# RoControl.net
KiCad netlist of a schematic drawn in Altium Designer
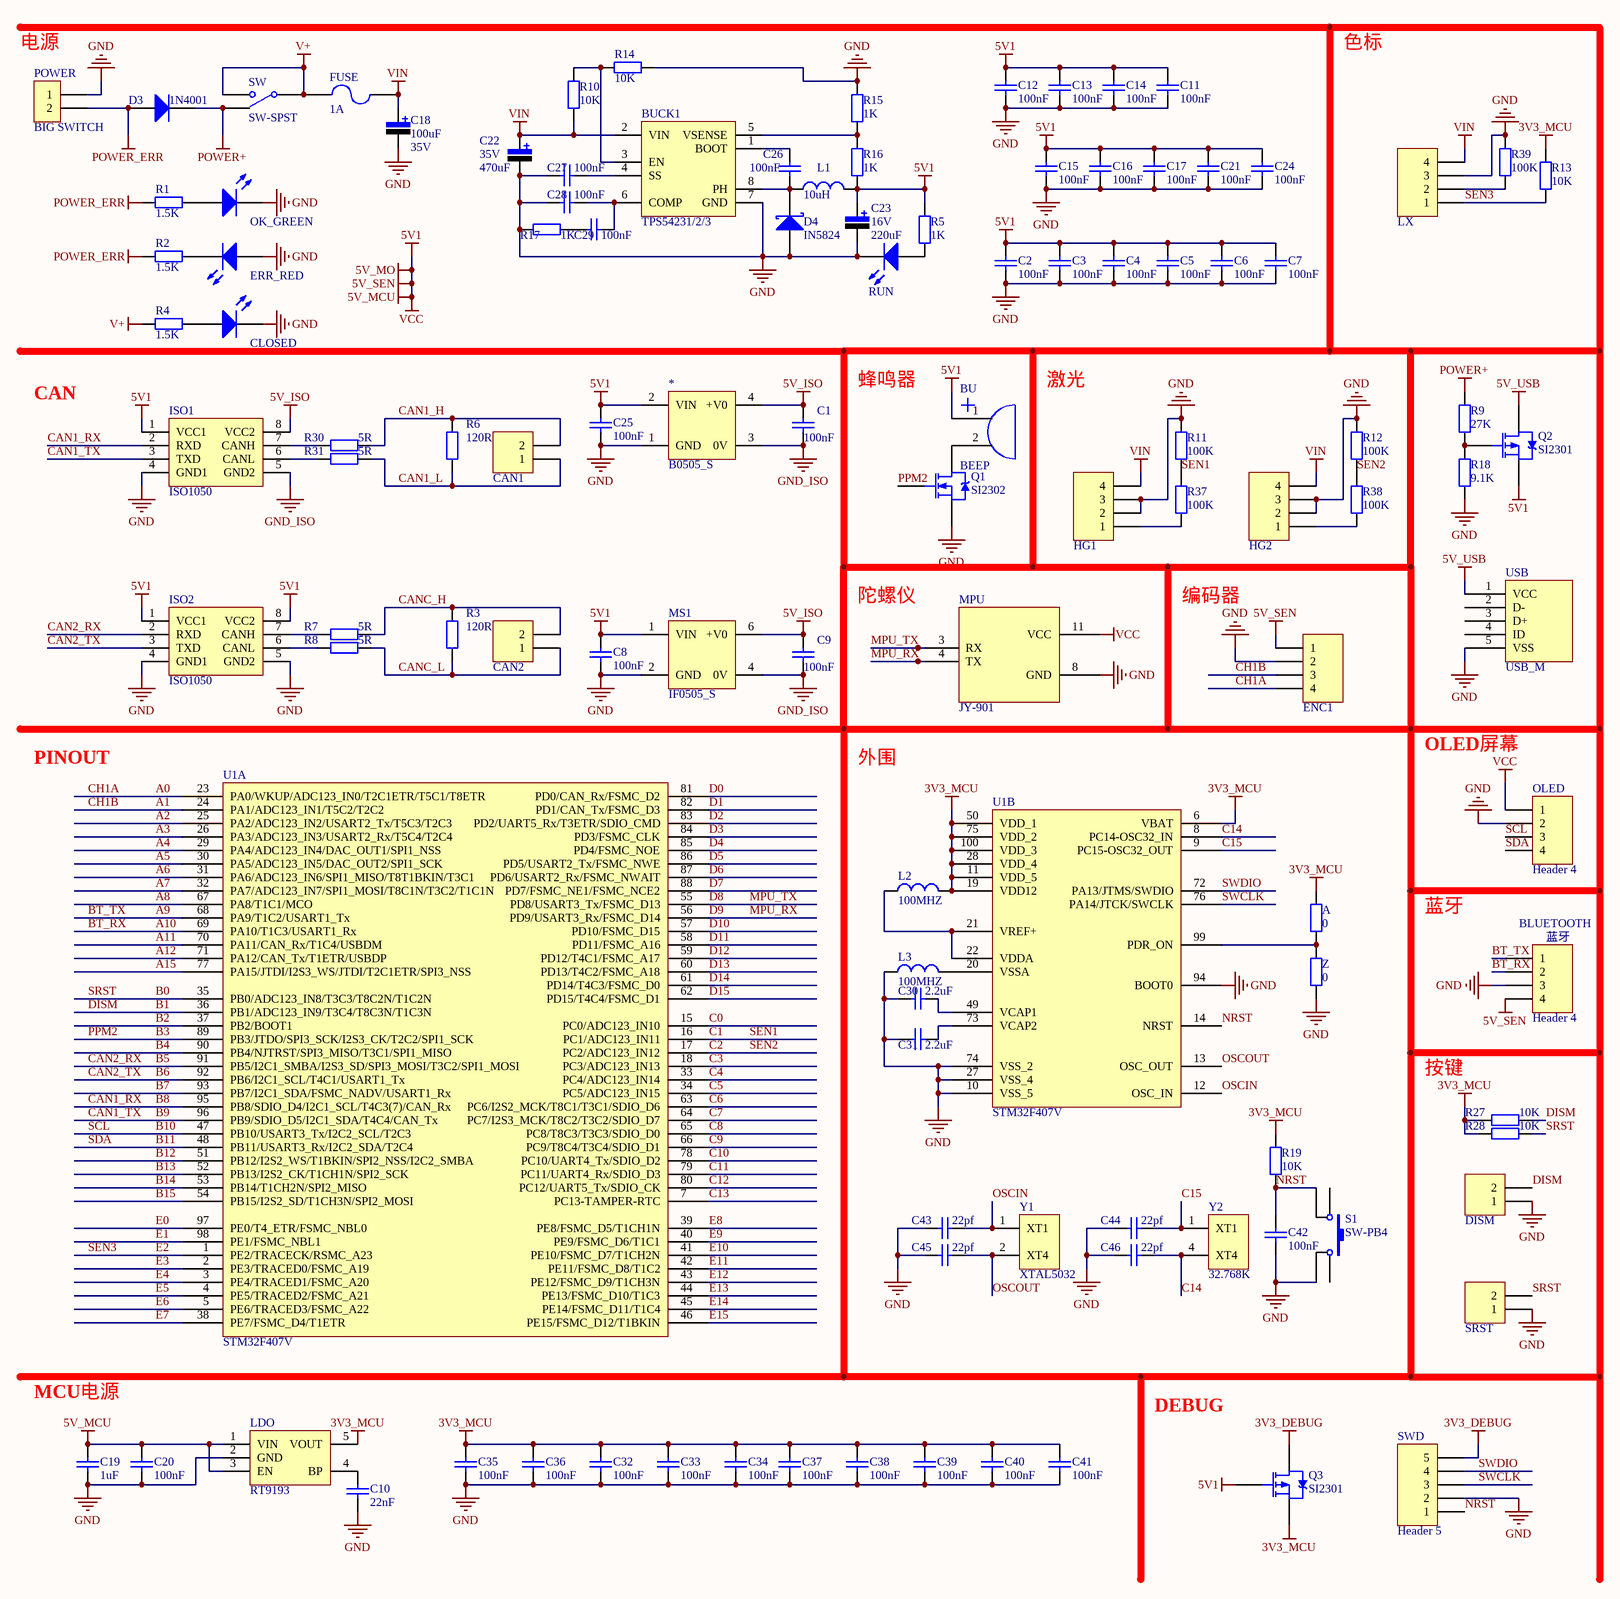
[diagram p0: RoControl.SchDoc]

(export (version "E")
  (design (tool "Eeschema 10.0.6"))
  (components
    (comp (ref "*")
      (value "B0505_S")
      (footprint "MORNSUN_SIP_S")
      (libsource (lib "RobocanControl") (part "B0505_S"))
    )
    (comp (ref "A")
      (value "0")
      (footprint "0603-1")
      (description "贴片电阻")
      (fields (field (name "Comment") "Res1") (field (name "PUBLISHER") "Altium Limited"))
      (libsource (lib "") (part "Res1_3"))
    )
    (comp (ref "BLUETOOTH")
      (value "Header 4")
      (footprint "HDR1X4")
      (description "Header, 4-Pin")
      (fields (field (name "PUBLISHER") "Altium Limited"))
      (libsource (lib "Miscellaneous Connectors") (part "Header 4"))
    )
    (comp (ref "BU")
      (value "BEEP")
      (footprint "CONTROL:BEEP")
      (description "蜂鸣器")
      (libsource (lib "Fszhang") (part "BEEP"))
    )
    (comp (ref "BUCK1")
      (value "TPS54231/2/3")
      (footprint "SOIC8_N")
      (libsource (lib "RobocanControl") (part "TPS54231/2/3"))
    )
    (comp (ref "C1")
      (value "100nF")
      (footprint "CAP-3528")
      (description "无极性电容")
      (fields (field (name "Comment") "Cap") (field (name "PUBLISHER") "Altium Limited"))
      (libsource (lib "Fszhang") (part "Cap"))
    )
    (comp (ref "C2")
      (value "100nF")
      (footprint "CAP-3528")
      (description "无极性电容")
      (fields (field (name "Comment") "Cap") (field (name "PUBLISHER") "Altium Limited"))
      (libsource (lib "Fszhang") (part "Cap"))
    )
    (comp (ref "C3")
      (value "100nF")
      (footprint "CAP-3528")
      (description "无极性电容")
      (fields (field (name "Comment") "Cap") (field (name "PUBLISHER") "Altium Limited"))
      (libsource (lib "Fszhang") (part "Cap"))
    )
    (comp (ref "C4")
      (value "100nF")
      (footprint "C-RAD-0805")
      (description "无极性电容")
      (fields (field (name "Comment") "Cap") (field (name "PUBLISHER") "Altium Limited"))
      (libsource (lib "Fszhang") (part "Cap"))
    )
    (comp (ref "C5")
      (value "100nF")
      (footprint "C-RAD-0805")
      (description "无极性电容")
      (fields (field (name "Comment") "Cap") (field (name "PUBLISHER") "Altium Limited"))
      (libsource (lib "Fszhang") (part "Cap"))
    )
    (comp (ref "C6")
      (value "100nF")
      (footprint "C-RAD-0805")
      (description "无极性电容")
      (fields (field (name "Comment") "Cap") (field (name "PUBLISHER") "Altium Limited"))
      (libsource (lib "Fszhang") (part "Cap"))
    )
    (comp (ref "C7")
      (value "100nF")
      (footprint "C-RAD-0805")
      (description "无极性电容")
      (fields (field (name "Comment") "Cap") (field (name "PUBLISHER") "Altium Limited"))
      (libsource (lib "Fszhang") (part "Cap"))
    )
    (comp (ref "C8")
      (value "100nF")
      (footprint "C-RAD-0805")
      (description "无极性电容")
      (fields (field (name "Comment") "Cap") (field (name "PUBLISHER") "Altium Limited"))
      (libsource (lib "Fszhang") (part "Cap"))
    )
    (comp (ref "C9")
      (value "100nF")
      (footprint "CAP-3528")
      (description "无极性电容")
      (fields (field (name "Comment") "Cap") (field (name "PUBLISHER") "Altium Limited"))
      (libsource (lib "Fszhang") (part "Cap"))
    )
    (comp (ref "C10")
      (value "22nF")
      (footprint "C-RAD-0805")
      (description "无极性电容")
      (fields (field (name "Comment") "Cap") (field (name "PUBLISHER") "Altium Limited"))
      (libsource (lib "Fszhang") (part "Cap"))
    )
    (comp (ref "C11")
      (value "100nF")
      (footprint "CAP-3528")
      (description "无极性电容")
      (fields (field (name "Comment") "Cap") (field (name "PUBLISHER") "Altium Limited"))
      (libsource (lib "Fszhang") (part "Cap"))
    )
    (comp (ref "C12")
      (value "100nF")
      (footprint "CAP-3528")
      (description "无极性电容")
      (fields (field (name "Comment") "Cap") (field (name "PUBLISHER") "Altium Limited"))
      (libsource (lib "Fszhang") (part "Cap"))
    )
    (comp (ref "C13")
      (value "100nF")
      (footprint "CAP-3528")
      (description "无极性电容")
      (fields (field (name "Comment") "Cap") (field (name "PUBLISHER") "Altium Limited"))
      (libsource (lib "Fszhang") (part "Cap"))
    )
    (comp (ref "C14")
      (value "100nF")
      (footprint "CAP-3528")
      (description "无极性电容")
      (fields (field (name "Comment") "Cap") (field (name "PUBLISHER") "Altium Limited"))
      (libsource (lib "Fszhang") (part "Cap"))
    )
    (comp (ref "C15")
      (value "100nF")
      (footprint "CAP-3528")
      (description "无极性电容")
      (fields (field (name "Comment") "Cap") (field (name "PUBLISHER") "Altium Limited"))
      (libsource (lib "Fszhang") (part "Cap"))
    )
    (comp (ref "C16")
      (value "100nF")
      (footprint "CAP-3528")
      (description "无极性电容")
      (fields (field (name "Comment") "Cap") (field (name "PUBLISHER") "Altium Limited"))
      (libsource (lib "Fszhang") (part "Cap"))
    )
    (comp (ref "C17")
      (value "100nF")
      (footprint "CAP-3528")
      (description "无极性电容")
      (fields (field (name "Comment") "Cap") (field (name "PUBLISHER") "Altium Limited"))
      (libsource (lib "Fszhang") (part "Cap"))
    )
    (comp (ref "C18")
      (value "100uF")
      (footprint "CAP-3528")
      (description "极性电解电容")
      (fields
        (field (name "VOL") "35V")
        (field (name "Comment") "Cap Pol")
        (field (name "PUBLISHER") "Altium Limited")
      )
      (libsource (lib "Fszhang") (part "Cap Pol"))
    )
    (comp (ref "C19")
      (value "1uF")
      (footprint "C-RAD-0805")
      (description "无极性电容")
      (fields (field (name "Comment") "Cap") (field (name "PUBLISHER") "Altium Limited"))
      (libsource (lib "Fszhang") (part "Cap"))
    )
    (comp (ref "C20")
      (value "100nF")
      (footprint "C-RAD-0805")
      (description "无极性电容")
      (fields (field (name "Comment") "Cap") (field (name "PUBLISHER") "Altium Limited"))
      (libsource (lib "Fszhang") (part "Cap"))
    )
    (comp (ref "C21")
      (value "100nF")
      (footprint "CAP-3528")
      (description "无极性电容")
      (fields (field (name "Comment") "Cap") (field (name "PUBLISHER") "Altium Limited"))
      (libsource (lib "Fszhang") (part "Cap"))
    )
    (comp (ref "C22")
      (value "470uF")
      (footprint "C-RB-8")
      (description "极性电解电容")
      (fields
        (field (name "VOL") "35V")
        (field (name "Comment") "Cap Pol")
        (field (name "PUBLISHER") "Altium Limited")
      )
      (libsource (lib "Fszhang") (part "Cap Pol"))
    )
    (comp (ref "C23")
      (value "220uF")
      (footprint "C-RB-8")
      (description "极性电解电容")
      (fields
        (field (name "VOL") "16V")
        (field (name "Comment") "Cap Pol")
        (field (name "PUBLISHER") "Altium Limited")
      )
      (libsource (lib "Fszhang") (part "Cap Pol"))
    )
    (comp (ref "C24")
      (value "100nF")
      (footprint "CAP-3528")
      (description "无极性电容")
      (fields (field (name "Comment") "Cap") (field (name "PUBLISHER") "Altium Limited"))
      (libsource (lib "Fszhang") (part "Cap"))
    )
    (comp (ref "C25")
      (value "100nF")
      (footprint "C-RAD-0805")
      (description "无极性电容")
      (fields (field (name "Comment") "Cap") (field (name "PUBLISHER") "Altium Limited"))
      (libsource (lib "Fszhang") (part "Cap"))
    )
    (comp (ref "C26")
      (value "100nF")
      (footprint "C-RAD-0805")
      (description "无极性电容")
      (fields (field (name "Comment") "Cap") (field (name "PUBLISHER") "Altium Limited"))
      (libsource (lib "Fszhang") (part "Cap"))
    )
    (comp (ref "C27")
      (value "100nF")
      (footprint "C-RAD-0805")
      (description "无极性电容")
      (fields (field (name "Comment") "Cap") (field (name "PUBLISHER") "Altium Limited"))
      (libsource (lib "Fszhang") (part "Cap"))
    )
    (comp (ref "C28")
      (value "100nF")
      (footprint "C-RAD-0805")
      (description "无极性电容")
      (fields (field (name "Comment") "Cap") (field (name "PUBLISHER") "Altium Limited"))
      (libsource (lib "Fszhang") (part "Cap"))
    )
    (comp (ref "C29")
      (value "100nF")
      (footprint "C-RAD-0805")
      (description "无极性电容")
      (fields (field (name "Comment") "Cap") (field (name "PUBLISHER") "Altium Limited"))
      (libsource (lib "Fszhang") (part "Cap"))
    )
    (comp (ref "C30")
      (value "2.2uF")
      (footprint "C-RAD-0805")
      (description "无极性电容")
      (fields (field (name "Comment") "Cap") (field (name "PUBLISHER") "Altium Limited"))
      (libsource (lib "Fszhang") (part "Cap"))
    )
    (comp (ref "C31")
      (value "2.2uF")
      (footprint "C-RAD-0805")
      (description "无极性电容")
      (fields (field (name "Comment") "Cap") (field (name "PUBLISHER") "Altium Limited"))
      (libsource (lib "Fszhang") (part "Cap"))
    )
    (comp (ref "C32")
      (value "100nF")
      (footprint "C-RAD-0805")
      (description "无极性电容")
      (fields (field (name "Comment") "Cap") (field (name "PUBLISHER") "Altium Limited"))
      (libsource (lib "Fszhang") (part "Cap"))
    )
    (comp (ref "C33")
      (value "100nF")
      (footprint "C-RAD-0805")
      (description "无极性电容")
      (fields (field (name "Comment") "Cap") (field (name "PUBLISHER") "Altium Limited"))
      (libsource (lib "Fszhang") (part "Cap"))
    )
    (comp (ref "C34")
      (value "100nF")
      (footprint "C-RAD-0805")
      (description "无极性电容")
      (fields (field (name "Comment") "Cap") (field (name "PUBLISHER") "Altium Limited"))
      (libsource (lib "Fszhang") (part "Cap"))
    )
    (comp (ref "C35")
      (value "100nF")
      (footprint "C-RAD-0805")
      (description "无极性电容")
      (fields (field (name "Comment") "Cap") (field (name "PUBLISHER") "Altium Limited"))
      (libsource (lib "Fszhang") (part "Cap"))
    )
    (comp (ref "C36")
      (value "100nF")
      (footprint "C-RAD-0805")
      (description "无极性电容")
      (fields (field (name "Comment") "Cap") (field (name "PUBLISHER") "Altium Limited"))
      (libsource (lib "Fszhang") (part "Cap"))
    )
    (comp (ref "C37")
      (value "100nF")
      (footprint "C-RAD-0805")
      (description "无极性电容")
      (fields (field (name "Comment") "Cap") (field (name "PUBLISHER") "Altium Limited"))
      (libsource (lib "Fszhang") (part "Cap"))
    )
    (comp (ref "C38")
      (value "100nF")
      (footprint "C-RAD-0805")
      (description "无极性电容")
      (fields (field (name "Comment") "Cap") (field (name "PUBLISHER") "Altium Limited"))
      (libsource (lib "Fszhang") (part "Cap"))
    )
    (comp (ref "C39")
      (value "100nF")
      (footprint "C-RAD-0805")
      (description "无极性电容")
      (fields (field (name "Comment") "Cap") (field (name "PUBLISHER") "Altium Limited"))
      (libsource (lib "Fszhang") (part "Cap"))
    )
    (comp (ref "C40")
      (value "100nF")
      (footprint "C-RAD-0805")
      (description "无极性电容")
      (fields (field (name "Comment") "Cap") (field (name "PUBLISHER") "Altium Limited"))
      (libsource (lib "Fszhang") (part "Cap"))
    )
    (comp (ref "C41")
      (value "100nF")
      (footprint "C-RAD-0805")
      (description "无极性电容")
      (fields (field (name "Comment") "Cap") (field (name "PUBLISHER") "Altium Limited"))
      (libsource (lib "Fszhang") (part "Cap"))
    )
    (comp (ref "C42")
      (value "100nF")
      (footprint "C-RAD-0805")
      (description "无极性电容")
      (fields (field (name "Comment") "Cap") (field (name "PUBLISHER") "Altium Limited"))
      (libsource (lib "Fszhang") (part "Cap"))
    )
    (comp (ref "C43")
      (value "22pf")
      (footprint "C-RAD-0603")
      (description "无极性电容")
      (fields (field (name "Comment") "Cap") (field (name "PUBLISHER") "Altium Limited"))
      (libsource (lib "Fszhang") (part "Cap"))
    )
    (comp (ref "C44")
      (value "22pf")
      (footprint "C-RAD-0603")
      (description "无极性电容")
      (fields (field (name "Comment") "Cap") (field (name "PUBLISHER") "Altium Limited"))
      (libsource (lib "Fszhang") (part "Cap"))
    )
    (comp (ref "C45")
      (value "22pf")
      (footprint "C-RAD-0603")
      (description "无极性电容")
      (fields (field (name "Comment") "Cap") (field (name "PUBLISHER") "Altium Limited"))
      (libsource (lib "Fszhang") (part "Cap"))
    )
    (comp (ref "C46")
      (value "22pf")
      (footprint "C-RAD-0603")
      (description "无极性电容")
      (fields (field (name "Comment") "Cap") (field (name "PUBLISHER") "Altium Limited"))
      (libsource (lib "Fszhang") (part "Cap"))
    )
    (comp (ref "CAN1")
      (value "Header 2")
      (footprint "HDR2X1_C")
      (description "接插件")
      (fields (field (name "PUBLISHER") "Altium Limited"))
      (libsource (lib "Fszhang") (part "Header 2"))
    )
    (comp (ref "CAN2")
      (value "Header 2")
      (footprint "HDR2X1_C")
      (description "接插件")
      (fields (field (name "PUBLISHER") "Altium Limited"))
      (libsource (lib "Fszhang") (part "Header 2"))
    )
    (comp (ref "CLOSED")
      (value "LED0")
      (footprint "LED_0805")
      (description "发光二极管")
      (fields (field (name "PUBLISHER") "Altium Limited"))
      (libsource (lib "Fszhang") (part "LED0"))
    )
    (comp (ref "D3")
      (value "Diode")
      (footprint "DIODE-SMA")
      (description "二极管")
      (fields (field (name "TYPE") "1N4001") (field (name "PUBLISHER") "Altium Limited"))
      (libsource (lib "Fszhang") (part "Diode"))
    )
    (comp (ref "D4")
      (value "D-Schottky")
      (footprint "DIODE-1206")
      (description "肖特基二极管")
      (fields (field (name "TYPE") "IN5824") (field (name "PUBLISHER") "Altium Limited"))
      (libsource (lib "Fszhang") (part "D-Schottky"))
    )
    (comp (ref "DISM")
      (value "Header 2")
      (footprint "HDR2X1_B1")
      (description "接插件")
      (fields (field (name "PUBLISHER") "Altium Limited"))
      (libsource (lib "Fszhang") (part "Header 2"))
    )
    (comp (ref "ENC1")
      (value "Header 4")
      (footprint "HDR4X1_B1")
      (description "接插件")
      (fields (field (name "PUBLISHER") "Altium Limited"))
      (libsource (lib "") (part "Header 4_1"))
    )
    (comp (ref "ERR_RED")
      (value "LED0")
      (footprint "LED_0805")
      (description "发光二极管")
      (fields (field (name "PUBLISHER") "Altium Limited"))
      (libsource (lib "Fszhang") (part "LED0"))
    )
    (comp (ref "FUSE")
      (value "1A")
      (footprint "1812")
      (description "保险丝")
      (fields (field (name "Comment") "Fuse") (field (name "PUBLISHER") "Altium Limited"))
      (libsource (lib "Fszhang") (part "Fuse 2"))
    )
    (comp (ref "HG1")
      (value "Header 4")
      (footprint "HDR4X1_B1")
      (description "接插件")
      (fields (field (name "PUBLISHER") "Altium Limited"))
      (libsource (lib "Fszhang") (part "Header 4"))
    )
    (comp (ref "HG2")
      (value "Header 4")
      (footprint "HDR4X1_B1")
      (description "接插件")
      (fields (field (name "PUBLISHER") "Altium Limited"))
      (libsource (lib "Fszhang") (part "Header 4"))
    )
    (comp (ref "ISO1")
      (value "ISO1050")
      (footprint "SOP254P1040X485-8N")
      (libsource (lib "RobocanControl") (part "ISO1050"))
    )
    (comp (ref "ISO2")
      (value "ISO1050")
      (footprint "SOP254P1040X485-8N")
      (libsource (lib "RobocanControl") (part "ISO1050"))
    )
    (comp (ref "L1")
      (value "10uH")
      (footprint "CD54")
      (description "电感")
      (fields (field (name "Comment") "Inductor") (field (name "PUBLISHER") "Altium Limited"))
      (libsource (lib "Fszhang") (part "Inductor"))
    )
    (comp (ref "L2")
      (value "100MHZ")
      (footprint "0805-1")
      (description "电感")
      (fields (field (name "Comment") "Inductor") (field (name "PUBLISHER") "Altium Limited"))
      (libsource (lib "Fszhang") (part "Inductor"))
    )
    (comp (ref "L3")
      (value "100MHZ")
      (footprint "0805-1")
      (description "电感")
      (fields (field (name "Comment") "Inductor") (field (name "PUBLISHER") "Altium Limited"))
      (libsource (lib "Fszhang") (part "Inductor"))
    )
    (comp (ref "LDO")
      (value "RT9193")
      (footprint "SOT104P300X129-5N")
      (libsource (lib "RobocanControl") (part "RT9193"))
    )
    (comp (ref "LX")
      (value "Header 4")
      (footprint "HDR4X1_B1")
      (description "接插件")
      (fields (field (name "PUBLISHER") "Altium Limited"))
      (libsource (lib "Fszhang") (part "Header 4"))
    )
    (comp (ref "MPU")
      (value "JY-901")
      (footprint "JY-901 - duplicate")
      (description "君悦智控高精度9轴传感器")
      (libsource (lib "RobocanControl") (part "JY-901"))
    )
    (comp (ref "MS1")
      (value "IF0505_S")
      (footprint "MORNSUN_SIP_LS")
      (libsource (lib "RobocanControl") (part "IF0505_S"))
    )
    (comp (ref "OK_GREEN")
      (value "LED0")
      (footprint "LED_0805")
      (description "发光二极管")
      (fields (field (name "PUBLISHER") "Altium Limited"))
      (libsource (lib "Fszhang") (part "LED0"))
    )
    (comp (ref "OLED")
      (value "Header 4")
      (footprint "HDR1X4")
      (description "Header, 4-Pin")
      (fields (field (name "PUBLISHER") "Altium Limited"))
      (libsource (lib "Miscellaneous Connectors") (part "Header 4"))
    )
    (comp (ref "POWER")
      (value "BIG SWITCH")
      (footprint "Header 2")
      (description "Header, 2-Pin")
      (fields (field (name "PUBLISHER") "Altium Limited"))
      (libsource (lib "RobocanControl") (part "Header 2 BIG"))
    )
    (comp (ref "Q1")
      (value "SI2302")
      (footprint "SOT-23_L")
      (description "HEXFET Power MOSFET")
      (fields (field (name "PUBLISHER") "Altium Limited"))
      (libsource (lib "IR Discrete MOSFET - Power") (part "IRLML2402"))
    )
    (comp (ref "Q2")
      (value "SI2301")
      (footprint "SOT-23_N")
      (description "HEXFET Power MOSFET")
      (fields (field (name "PUBLISHER") "Altium Limited"))
      (libsource (lib "IR Discrete MOSFET - Power") (part "IRLML5103"))
    )
    (comp (ref "Q3")
      (value "SI2301")
      (footprint "SOT-23_N")
      (description "HEXFET Power MOSFET")
      (fields (field (name "PUBLISHER") "Altium Limited"))
      (libsource (lib "IR Discrete MOSFET - Power") (part "IRLML5103"))
    )
    (comp (ref "R1")
      (value "1.5K")
      (footprint "0805-1")
      (description "贴片电阻")
      (fields (field (name "Comment") "Res1") (field (name "PUBLISHER") "Altium Limited"))
      (libsource (lib "Fszhang") (part "Res1"))
    )
    (comp (ref "R2")
      (value "1.5K")
      (footprint "0805-1")
      (description "贴片电阻")
      (fields (field (name "Comment") "Res1") (field (name "PUBLISHER") "Altium Limited"))
      (libsource (lib "Fszhang") (part "Res1"))
    )
    (comp (ref "R3")
      (value "120R")
      (footprint "1206")
      (description "贴片电阻")
      (fields (field (name "Comment") "Res1") (field (name "PUBLISHER") "Altium Limited"))
      (libsource (lib "") (part "Res1_1"))
    )
    (comp (ref "R4")
      (value "1.5K")
      (footprint "0805-1")
      (description "贴片电阻")
      (fields (field (name "Comment") "Res1") (field (name "PUBLISHER") "Altium Limited"))
      (libsource (lib "") (part "Res1_2"))
    )
    (comp (ref "R5")
      (value "1K")
      (footprint "0805-1")
      (description "贴片电阻")
      (fields (field (name "Comment") "Res1") (field (name "PUBLISHER") "Altium Limited"))
      (libsource (lib "") (part "Res1_1"))
    )
    (comp (ref "R6")
      (value "120R")
      (footprint "1206")
      (description "贴片电阻")
      (fields (field (name "Comment") "Res1") (field (name "PUBLISHER") "Altium Limited"))
      (libsource (lib "") (part "Res1_1"))
    )
    (comp (ref "R7")
      (value "5R")
      (footprint "0805-1")
      (description "贴片电阻")
      (fields (field (name "Comment") "Res1") (field (name "PUBLISHER") "Altium Limited"))
      (libsource (lib "") (part "Res1_2"))
    )
    (comp (ref "R8")
      (value "5R")
      (footprint "0805-1")
      (description "贴片电阻")
      (fields (field (name "Comment") "Res1") (field (name "PUBLISHER") "Altium Limited"))
      (libsource (lib "") (part "Res1_2"))
    )
    (comp (ref "R9")
      (value "27K")
      (footprint "0805-1")
      (description "贴片电阻")
      (fields (field (name "Comment") "Res1") (field (name "PUBLISHER") "Altium Limited"))
      (libsource (lib "fszhang") (part "Res1"))
    )
    (comp (ref "R10")
      (value "10K")
      (footprint "0805-1")
      (description "贴片电阻")
      (fields (field (name "Comment") "Res1") (field (name "PUBLISHER") "Altium Limited"))
      (libsource (lib "") (part "Res1_1"))
    )
    (comp (ref "R11")
      (value "100K")
      (footprint "0805-1")
      (description "贴片电阻")
      (fields (field (name "Comment") "Res1") (field (name "PUBLISHER") "Altium Limited"))
      (libsource (lib "") (part "Res1_1"))
    )
    (comp (ref "R12")
      (value "100K")
      (footprint "0805-1")
      (description "贴片电阻")
      (fields (field (name "Comment") "Res1") (field (name "PUBLISHER") "Altium Limited"))
      (libsource (lib "") (part "Res1_1"))
    )
    (comp (ref "R13")
      (value "10K")
      (footprint "0805-1")
      (description "贴片电阻")
      (fields (field (name "Comment") "Res1") (field (name "PUBLISHER") "Altium Limited"))
      (libsource (lib "") (part "Res1_1"))
    )
    (comp (ref "R14")
      (value "10K")
      (footprint "0805-1")
      (description "贴片电阻")
      (fields (field (name "Comment") "Res1") (field (name "PUBLISHER") "Altium Limited"))
      (libsource (lib "Fszhang") (part "Res1"))
    )
    (comp (ref "R15")
      (value "1K")
      (footprint "0805-1")
      (description "贴片电阻")
      (fields (field (name "Comment") "Res1") (field (name "PUBLISHER") "Altium Limited"))
      (libsource (lib "") (part "Res1_1"))
    )
    (comp (ref "R16")
      (value "1K")
      (footprint "0805-1")
      (description "贴片电阻")
      (fields (field (name "Comment") "Res1") (field (name "PUBLISHER") "Altium Limited"))
      (libsource (lib "") (part "Res1_1"))
    )
    (comp (ref "R17")
      (value "1K")
      (footprint "0805-1")
      (description "贴片电阻")
      (fields (field (name "Comment") "Res1") (field (name "PUBLISHER") "Altium Limited"))
      (libsource (lib "Fszhang") (part "Res1"))
    )
    (comp (ref "R18")
      (value "9.1K")
      (footprint "0805-1")
      (description "贴片电阻")
      (fields (field (name "Comment") "Res1") (field (name "PUBLISHER") "Altium Limited"))
      (libsource (lib "fszhang") (part "Res1"))
    )
    (comp (ref "R19")
      (value "10K")
      (footprint "0805-1")
      (description "贴片电阻")
      (fields (field (name "Comment") "Res1") (field (name "PUBLISHER") "Altium Limited"))
      (libsource (lib "") (part "Res1_1"))
    )
    (comp (ref "R27")
      (value "10K")
      (footprint "0805-1")
      (description "贴片电阻")
      (fields (field (name "Comment") "Res1") (field (name "PUBLISHER") "Altium Limited"))
      (libsource (lib "Fszhang") (part "Res1"))
    )
    (comp (ref "R28")
      (value "10K")
      (footprint "0805-1")
      (description "贴片电阻")
      (fields (field (name "Comment") "Res1") (field (name "PUBLISHER") "Altium Limited"))
      (libsource (lib "Fszhang") (part "Res1"))
    )
    (comp (ref "R30")
      (value "5R")
      (footprint "0805-1")
      (description "贴片电阻")
      (fields (field (name "Comment") "Res1") (field (name "PUBLISHER") "Altium Limited"))
      (libsource (lib "") (part "Res1_2"))
    )
    (comp (ref "R31")
      (value "5R")
      (footprint "0805-1")
      (description "贴片电阻")
      (fields (field (name "Comment") "Res1") (field (name "PUBLISHER") "Altium Limited"))
      (libsource (lib "") (part "Res1_2"))
    )
    (comp (ref "R37")
      (value "100K")
      (footprint "0805-1")
      (description "贴片电阻")
      (fields (field (name "Comment") "Res1") (field (name "PUBLISHER") "Altium Limited"))
      (libsource (lib "") (part "Res1_1"))
    )
    (comp (ref "R38")
      (value "100K")
      (footprint "0805-1")
      (description "贴片电阻")
      (fields (field (name "Comment") "Res1") (field (name "PUBLISHER") "Altium Limited"))
      (libsource (lib "") (part "Res1_1"))
    )
    (comp (ref "R39")
      (value "100K")
      (footprint "0805-1")
      (description "贴片电阻")
      (fields (field (name "Comment") "Res1") (field (name "PUBLISHER") "Altium Limited"))
      (libsource (lib "") (part "Res1_1"))
    )
    (comp (ref "RUN")
      (value "LED0")
      (footprint "LED_0805")
      (description "发光二极管")
      (fields (field (name "PUBLISHER") "Altium Limited"))
      (libsource (lib "Fszhang") (part "LED0"))
    )
    (comp (ref "S1")
      (value "SW-PB4")
      (footprint "SW_PB4_A1")
      (description "微动开关")
      (fields (field (name "PUBLISHER") "Altium Limited"))
      (libsource (lib "Fszhang") (part "SW-PB4"))
    )
    (comp (ref "SRST")
      (value "Header 2")
      (footprint "HDR2X1_B1")
      (description "接插件")
      (fields (field (name "PUBLISHER") "Altium Limited"))
      (libsource (lib "Fszhang") (part "Header 2"))
    )
    (comp (ref "SW")
      (value "SW-SPST")
      (footprint "SW-SPST")
      (description "Single-Pole, Single-Throw Switch")
      (fields (field (name "PUBLISHER") "Altium Limited"))
      (libsource (lib "jxt") (part "SW-SPST"))
    )
    (comp (ref "SWD")
      (value "Header 5")
      (footprint "HDR1X5")
      (description "Header, 5-Pin")
      (fields (field (name "PUBLISHER") "Altium Limited"))
      (libsource (lib "Miscellaneous Connectors") (part "Header 5"))
    )
    (comp (ref "U1")
      (value "STM32F407V")
      (footprint "LQFP-100_M")
      (description "STM32单片机100引脚")
      (libsource (lib "Fszhang") (part "STM32F407V"))
    )
    (comp (ref "USB")
      (value "USB_M")
      (footprint "USB_MICRO")
      (description "MicroUSB接口")
      (libsource (lib "CONTROL") (part "USB_M"))
    )
    (comp (ref "Y1") (value "XTAL5032") (footprint "XTAL_5032") (libsource (lib "CONTROL") (part "XTAL5032")))
    (comp (ref "Y2") (value "32.768K") (footprint "32.768K_SMD") (libsource (lib "CONTROL") (part "32.768K")))
    (comp (ref "Z")
      (value "0")
      (footprint "0603-1")
      (description "贴片电阻")
      (fields (field (name "Comment") "Res1") (field (name "PUBLISHER") "Altium Limited"))
      (libsource (lib "") (part "Res1_3"))
    )
  )
  (nets
    (net (code "1") (name "/A0") (class "Default")
      (node (ref "ENC1") (pin "4") (pinfunction "4_4") (pintype "passive"))
      (node (ref "U1") (pin "23") (pinfunction "PA0/WKUP/ADC123_IN0/T2C1ETR/T5C1/T8ETR_23") (pintype "passive"))
    )
    (net (code "2") (name "/A1") (class "Default")
      (node (ref "ENC1") (pin "3") (pinfunction "3_3") (pintype "passive"))
      (node (ref "U1") (pin "24") (pinfunction "PA1/ADC123_IN1/T5C2/T2C2_24") (pintype "passive"))
    )
    (net (code "3") (name "/A2") (class "Default")
      (node (ref "U1") (pin "25") (pinfunction "PA2/ADC123_IN2/USART2_Tx/T5C3/T2C3_25") (pintype "passive"))
    )
    (net (code "4") (name "/A3") (class "Default")
      (node (ref "U1") (pin "26") (pinfunction "PA3/ADC123_IN3/USART2_Rx/T5C4/T2C4_26") (pintype "passive"))
    )
    (net (code "5") (name "/A4") (class "Default")
      (node (ref "U1") (pin "29") (pinfunction "PA4/ADC123_IN4/DAC_OUT1/SPI1_NSS_29") (pintype "passive"))
    )
    (net (code "6") (name "/A5") (class "Default")
      (node (ref "U1") (pin "30") (pinfunction "PA5/ADC123_IN5/DAC_OUT2/SPI1_SCK_30") (pintype "passive"))
    )
    (net (code "7") (name "/A6") (class "Default")
      (node (ref "U1") (pin "31") (pinfunction "PA6/ADC123_IN6/SPI1_MISO/T8T1BKIN/T3C1_31") (pintype "passive"))
    )
    (net (code "8") (name "/A7") (class "Default")
      (node (ref "U1") (pin "32") (pinfunction "PA7/ADC123_IN7/SPI1_MOSI/T8C1N/T3C2/T1C1N_32") (pintype "passive"))
    )
    (net (code "9") (name "/A8") (class "Default")
      (node (ref "U1") (pin "67") (pinfunction "PA8/T1C1/MCO_67") (pintype "passive"))
    )
    (net (code "10") (name "/A9") (class "Default")
      (node (ref "BLUETOOTH") (pin "1") (pinfunction "1_1") (pintype "passive"))
      (node (ref "U1") (pin "68") (pinfunction "PA9/T1C2/USART1_Tx_68") (pintype "passive"))
    )
    (net (code "11") (name "/A10") (class "Default")
      (node (ref "BLUETOOTH") (pin "2") (pinfunction "2_2") (pintype "passive"))
      (node (ref "U1") (pin "69") (pinfunction "PA10/T1C3/USART1_Rx_69") (pintype "passive"))
    )
    (net (code "12") (name "/A11") (class "Default")
      (node (ref "U1") (pin "70") (pinfunction "PA11/CAN_Rx/T1C4/USBDM_70") (pintype "passive"))
    )
    (net (code "13") (name "/A12") (class "Default")
      (node (ref "U1") (pin "71") (pinfunction "PA12/CAN_Tx/T1ETR/USBDP_71") (pintype "passive"))
    )
    (net (code "14") (name "/A15") (class "Default")
      (node (ref "U1") (pin "77") (pinfunction "PA15/JTDI/I2S3_WS/JTDI/T2C1ETR/SPI3_NSS_77") (pintype "passive"))
    )
    (net (code "15") (name "/B0") (class "Default")
      (node (ref "R28") (pin "2") (pinfunction "2_2") (pintype "passive"))
      (node (ref "SRST") (pin "2") (pinfunction "2_2") (pintype "passive"))
      (node (ref "U1") (pin "35") (pinfunction "PB0/ADC123_IN8/T3C3/T8C2N/T1C2N_35") (pintype "passive"))
    )
    (net (code "16") (name "/B1") (class "Default")
      (node (ref "DISM") (pin "2") (pinfunction "2_2") (pintype "passive"))
      (node (ref "R27") (pin "2") (pinfunction "2_2") (pintype "passive"))
      (node (ref "U1") (pin "36") (pinfunction "PB1/ADC123_IN9/T3C4/T8C3N/T1C3N_36") (pintype "passive"))
    )
    (net (code "17") (name "/B2") (class "Default")
      (node (ref "U1") (pin "37") (pinfunction "PB2/BOOT1_37") (pintype "passive"))
    )
    (net (code "18") (name "/B3") (class "Default")
      (node (ref "Q1") (pin "1") (pinfunction "G_1") (pintype "passive"))
      (node (ref "U1") (pin "89") (pinfunction "PB3/JTDO/SPI3_SCK/I2S3_CK/T2C2/SPI1_SCK_89") (pintype "passive"))
    )
    (net (code "19") (name "/B4") (class "Default")
      (node (ref "U1") (pin "90") (pinfunction "PB4/NJTRST/SPI3_MISO/T3C1/SPI1_MISO_90") (pintype "passive"))
    )
    (net (code "20") (name "/B5") (class "Default")
      (node (ref "ISO2") (pin "2") (pinfunction "RXD_2") (pintype "passive"))
      (node (ref "U1") (pin "91") (pinfunction "PB5/I2C1_SMBA/I2S3_SD/SPI3_MOSI/T3C2/SPI1_MOSI_91") (pintype "passive"))
    )
    (net (code "21") (name "/B6") (class "Default")
      (node (ref "ISO2") (pin "3") (pinfunction "TXD_3") (pintype "passive"))
      (node (ref "U1") (pin "92") (pinfunction "PB6/I2C1_SCL/T4C1/USART1_Tx_92") (pintype "passive"))
    )
    (net (code "22") (name "/B7") (class "Default")
      (node (ref "U1") (pin "93") (pinfunction "PB7/I2C1_SDA/FSMC_NADV/USART1_Rx_93") (pintype "passive"))
    )
    (net (code "23") (name "/B8") (class "Default")
      (node (ref "ISO1") (pin "2") (pinfunction "RXD_2") (pintype "passive"))
      (node (ref "U1") (pin "95") (pinfunction "PB8/SDIO_D4/I2C1_SCL/T4C3(7)/CAN_Rx_95") (pintype "passive"))
    )
    (net (code "24") (name "/B9") (class "Default")
      (node (ref "ISO1") (pin "3") (pinfunction "TXD_3") (pintype "passive"))
      (node (ref "U1") (pin "96") (pinfunction "PB9/SDIO_D5/I2C1_SDA/T4C4/CAN_Tx_96") (pintype "passive"))
    )
    (net (code "25") (name "/B10") (class "Default")
      (node (ref "OLED") (pin "3") (pinfunction "3_3") (pintype "passive"))
      (node (ref "U1") (pin "47") (pinfunction "PB10/USART3_Tx/I2C2_SCL/T2C3_47") (pintype "passive"))
    )
    (net (code "26") (name "/B11") (class "Default")
      (node (ref "OLED") (pin "4") (pinfunction "4_4") (pintype "passive"))
      (node (ref "U1") (pin "48") (pinfunction "PB11/USART3_Rx/I2C2_SDA/T2C4_48") (pintype "passive"))
    )
    (net (code "27") (name "/B12") (class "Default")
      (node (ref "U1") (pin "51") (pinfunction "PB12/I2S2_WS/T1BKIN/SPI2_NSS/I2C2_SMBA_51") (pintype "passive"))
    )
    (net (code "28") (name "/B13") (class "Default")
      (node (ref "U1") (pin "52") (pinfunction "PB13/I2S2_CK/T1CH1N/SPI2_SCK_52") (pintype "passive"))
    )
    (net (code "29") (name "/B14") (class "Default")
      (node (ref "U1") (pin "53") (pinfunction "PB14/T1CH2N/SPI2_MISO_53") (pintype "passive"))
    )
    (net (code "30") (name "/B15") (class "Default")
      (node (ref "U1") (pin "54") (pinfunction "PB15/I2S2_SD/T1CH3N/SPI2_MOSI_54") (pintype "passive"))
    )
    (net (code "31") (name "/C0") (class "Default")
      (node (ref "U1") (pin "15") (pinfunction "PC0/ADC123_IN10_15") (pintype "passive"))
    )
    (net (code "32") (name "/C1") (class "Default")
      (node (ref "R11") (pin "1") (pinfunction "1_1") (pintype "passive"))
      (node (ref "R37") (pin "2") (pinfunction "2_2") (pintype "passive"))
      (node (ref "U1") (pin "16") (pinfunction "PC1/ADC123_IN11_16") (pintype "passive"))
    )
    (net (code "33") (name "/C2") (class "Default")
      (node (ref "R12") (pin "1") (pinfunction "1_1") (pintype "passive"))
      (node (ref "R38") (pin "2") (pinfunction "2_2") (pintype "passive"))
      (node (ref "U1") (pin "17") (pinfunction "PC2/ADC123_IN12_17") (pintype "passive"))
    )
    (net (code "34") (name "/C3") (class "Default")
      (node (ref "U1") (pin "18") (pinfunction "PC3/ADC123_IN13_18") (pintype "passive"))
    )
    (net (code "35") (name "/C4") (class "Default")
      (node (ref "U1") (pin "33") (pinfunction "PC4/ADC123_IN14_33") (pintype "passive"))
    )
    (net (code "36") (name "/C5") (class "Default")
      (node (ref "U1") (pin "34") (pinfunction "PC5/ADC123_IN15_34") (pintype "passive"))
    )
    (net (code "37") (name "/C6") (class "Default")
      (node (ref "U1") (pin "63") (pinfunction "PC6/I2S2_MCK/T8C1/T3C1/SDIO_D6_63") (pintype "passive"))
    )
    (net (code "38") (name "/C7") (class "Default")
      (node (ref "U1") (pin "64") (pinfunction "PC7/I2S3_MCK/T8C2/T3C2/SDIO_D7_64") (pintype "passive"))
    )
    (net (code "39") (name "/C8") (class "Default")
      (node (ref "U1") (pin "65") (pinfunction "PC8/T8C3/T3C3/SDIO_D0_65") (pintype "passive"))
    )
    (net (code "40") (name "/C9") (class "Default")
      (node (ref "U1") (pin "66") (pinfunction "PC9/T8C4/T3C4/SDIO_D1_66") (pintype "passive"))
    )
    (net (code "41") (name "/C10") (class "Default")
      (node (ref "U1") (pin "78") (pinfunction "PC10/UART4_Tx/SDIO_D2_78") (pintype "passive"))
    )
    (net (code "42") (name "/C11") (class "Default")
      (node (ref "U1") (pin "79") (pinfunction "PC11/UART4_Rx/SDIO_D3_79") (pintype "passive"))
    )
    (net (code "43") (name "/C12") (class "Default")
      (node (ref "U1") (pin "80") (pinfunction "PC12/UART5_Tx/SDIO_CK_80") (pintype "passive"))
    )
    (net (code "44") (name "/C13") (class "Default")
      (node (ref "U1") (pin "7") (pinfunction "PC13-TAMPER-RTC_7") (pintype "passive"))
    )
    (net (code "45") (name "/C14") (class "Default")
      (node (ref "C46") (pin "2") (pinfunction "2_2") (pintype "passive"))
      (node (ref "U1") (pin "8") (pinfunction "PC14-OSC32_IN_8") (pintype "passive"))
      (node (ref "Y2") (pin "4") (pinfunction "XT4_4") (pintype "passive"))
    )
    (net (code "46") (name "/C15") (class "Default")
      (node (ref "C44") (pin "2") (pinfunction "2_2") (pintype "passive"))
      (node (ref "U1") (pin "9") (pinfunction "PC15-OSC32_OUT_9") (pintype "passive"))
      (node (ref "Y2") (pin "1") (pinfunction "XT1_1") (pintype "passive"))
    )
    (net (code "47") (name "/CAN1_H") (class "Default")
      (node (ref "CAN1") (pin "2") (pinfunction "2_2") (pintype "passive"))
      (node (ref "R30") (pin "1") (pinfunction "1_1") (pintype "passive"))
      (node (ref "R6") (pin "2") (pinfunction "2_2") (pintype "passive"))
    )
    (net (code "48") (name "/CAN1_L") (class "Default")
      (node (ref "CAN1") (pin "1") (pinfunction "1_1") (pintype "passive"))
      (node (ref "R31") (pin "1") (pinfunction "1_1") (pintype "passive"))
      (node (ref "R6") (pin "1") (pinfunction "1_1") (pintype "passive"))
    )
    (net (code "49") (name "/CANC_H") (class "Default")
      (node (ref "CAN2") (pin "2") (pinfunction "2_2") (pintype "passive"))
      (node (ref "R3") (pin "2") (pinfunction "2_2") (pintype "passive"))
      (node (ref "R7") (pin "1") (pinfunction "1_1") (pintype "passive"))
    )
    (net (code "50") (name "/CANC_L") (class "Default")
      (node (ref "CAN2") (pin "1") (pinfunction "1_1") (pintype "passive"))
      (node (ref "R3") (pin "1") (pinfunction "1_1") (pintype "passive"))
      (node (ref "R8") (pin "1") (pinfunction "1_1") (pintype "passive"))
    )
    (net (code "51") (name "/D0") (class "Default")
      (node (ref "U1") (pin "81") (pinfunction "PD0/CAN_Rx/FSMC_D2_81") (pintype "passive"))
    )
    (net (code "52") (name "/D1") (class "Default")
      (node (ref "U1") (pin "82") (pinfunction "PD1/CAN_Tx/FSMC_D3_82") (pintype "passive"))
    )
    (net (code "53") (name "/D2") (class "Default")
      (node (ref "U1") (pin "83") (pinfunction "PD2/UART5_Rx/T3ETR/SDIO_CMD_83") (pintype "passive"))
    )
    (net (code "54") (name "/D3") (class "Default")
      (node (ref "U1") (pin "84") (pinfunction "PD3/FSMC_CLK_84") (pintype "passive"))
    )
    (net (code "55") (name "/D4") (class "Default")
      (node (ref "U1") (pin "85") (pinfunction "PD4/FSMC_NOE_85") (pintype "passive"))
    )
    (net (code "56") (name "/D5") (class "Default")
      (node (ref "U1") (pin "86") (pinfunction "PD5/USART2_Tx/FSMC_NWE_86") (pintype "passive"))
    )
    (net (code "57") (name "/D6") (class "Default")
      (node (ref "U1") (pin "87") (pinfunction "PD6/USART2_Rx/FSMC_NWAIT_87") (pintype "passive"))
    )
    (net (code "58") (name "/D7") (class "Default")
      (node (ref "U1") (pin "88") (pinfunction "PD7/FSMC_NE1/FSMC_NCE2_88") (pintype "passive"))
    )
    (net (code "59") (name "/D8") (class "Default")
      (node (ref "MPU") (pin "3") (pinfunction "RX_3") (pintype "passive"))
      (node (ref "U1") (pin "55") (pinfunction "PD8/USART3_Tx/FSMC_D13_55") (pintype "passive"))
    )
    (net (code "60") (name "/D9") (class "Default")
      (node (ref "MPU") (pin "4") (pinfunction "TX_4") (pintype "passive"))
      (node (ref "U1") (pin "56") (pinfunction "PD9/USART3_Rx/FSMC_D14_56") (pintype "passive"))
    )
    (net (code "61") (name "/D10") (class "Default")
      (node (ref "U1") (pin "57") (pinfunction "PD10/FSMC_D15_57") (pintype "passive"))
    )
    (net (code "62") (name "/D11") (class "Default")
      (node (ref "U1") (pin "58") (pinfunction "PD11/FSMC_A16_58") (pintype "passive"))
    )
    (net (code "63") (name "/D12") (class "Default")
      (node (ref "U1") (pin "59") (pinfunction "PD12/T4C1/FSMC_A17_59") (pintype "passive"))
    )
    (net (code "64") (name "/D13") (class "Default")
      (node (ref "U1") (pin "60") (pinfunction "PD13/T4C2/FSMC_A18_60") (pintype "passive"))
    )
    (net (code "65") (name "/D14") (class "Default")
      (node (ref "U1") (pin "61") (pinfunction "PD14/T4C3/FSMC_D0_61") (pintype "passive"))
    )
    (net (code "66") (name "/D15") (class "Default")
      (node (ref "U1") (pin "62") (pinfunction "PD15/T4C4/FSMC_D1_62") (pintype "passive"))
    )
    (net (code "67") (name "/E0") (class "Default")
      (node (ref "U1") (pin "97") (pinfunction "PE0/T4_ETR/FSMC_NBL0_97") (pintype "passive"))
    )
    (net (code "68") (name "/E1") (class "Default")
      (node (ref "U1") (pin "98") (pinfunction "PE1/FSMC_NBL1_98") (pintype "passive"))
    )
    (net (code "69") (name "/E2") (class "Default")
      (node (ref "LX") (pin "1") (pinfunction "1_1") (pintype "passive"))
      (node (ref "R13") (pin "1") (pinfunction "1_1") (pintype "passive"))
      (node (ref "U1") (pin "1") (pinfunction "PE2/TRACECK/RSMC_A23_1") (pintype "passive"))
    )
    (net (code "70") (name "/E3") (class "Default")
      (node (ref "U1") (pin "2") (pinfunction "PE3/TRACED0/FSMC_A19_2") (pintype "passive"))
    )
    (net (code "71") (name "/E4") (class "Default")
      (node (ref "U1") (pin "3") (pinfunction "PE4/TRACED1/FSMC_A20_3") (pintype "passive"))
    )
    (net (code "72") (name "/E5") (class "Default")
      (node (ref "U1") (pin "4") (pinfunction "PE5/TRACED2/FSMC_A21_4") (pintype "passive"))
    )
    (net (code "73") (name "/E6") (class "Default")
      (node (ref "U1") (pin "5") (pinfunction "PE6/TRACED3/FSMC_A22_5") (pintype "passive"))
    )
    (net (code "74") (name "/E7") (class "Default")
      (node (ref "U1") (pin "38") (pinfunction "PE7/FSMC_D4/T1ETR_38") (pintype "passive"))
    )
    (net (code "75") (name "/E8") (class "Default")
      (node (ref "U1") (pin "39") (pinfunction "PE8/FSMC_D5/T1CH1N_39") (pintype "passive"))
    )
    (net (code "76") (name "/E9") (class "Default")
      (node (ref "U1") (pin "40") (pinfunction "PE9/FSMC_D6/T1C1_40") (pintype "passive"))
    )
    (net (code "77") (name "/E10") (class "Default")
      (node (ref "U1") (pin "41") (pinfunction "PE10/FSMC_D7/T1CH2N_41") (pintype "passive"))
    )
    (net (code "78") (name "/E11") (class "Default")
      (node (ref "U1") (pin "42") (pinfunction "PE11/FSMC_D8/T1C2_42") (pintype "passive"))
    )
    (net (code "79") (name "/E12") (class "Default")
      (node (ref "U1") (pin "43") (pinfunction "PE12/FSMC_D9/T1CH3N_43") (pintype "passive"))
    )
    (net (code "80") (name "/E13") (class "Default")
      (node (ref "U1") (pin "44") (pinfunction "PE13/FSMC_D10/T1C3_44") (pintype "passive"))
    )
    (net (code "81") (name "/E14") (class "Default")
      (node (ref "U1") (pin "45") (pinfunction "PE14/FSMC_D11/T1C4_45") (pintype "passive"))
    )
    (net (code "82") (name "/E15") (class "Default")
      (node (ref "U1") (pin "46") (pinfunction "PE15/FSMC_D12/T1BKIN_46") (pintype "passive"))
    )
    (net (code "83") (name "/NRST") (class "Default")
      (node (ref "C42") (pin "2") (pinfunction "2_2") (pintype "passive"))
      (node (ref "R19") (pin "1") (pinfunction "1_1") (pintype "passive"))
      (node (ref "S1") (pin "4") (pinfunction "4_4") (pintype "passive"))
      (node (ref "SWD") (pin "1") (pinfunction "1_1") (pintype "passive"))
      (node (ref "U1") (pin "14") (pinfunction "NRST_14") (pintype "passive"))
    )
    (net (code "84") (name "/OSCIN") (class "Default")
      (node (ref "C43") (pin "2") (pinfunction "2_2") (pintype "passive"))
      (node (ref "U1") (pin "12") (pinfunction "OSC_IN_12") (pintype "passive"))
      (node (ref "Y1") (pin "1") (pinfunction "XT1_1") (pintype "passive"))
    )
    (net (code "85") (name "/OSCOUT") (class "Default")
      (node (ref "C45") (pin "2") (pinfunction "2_2") (pintype "passive"))
      (node (ref "U1") (pin "13") (pinfunction "OSC_OUT_13") (pintype "passive"))
      (node (ref "Y1") (pin "2") (pinfunction "XT4_2") (pintype "passive"))
    )
    (net (code "86") (name "/SWCLK") (class "Default")
      (node (ref "SWD") (pin "3") (pinfunction "3_3") (pintype "passive"))
      (node (ref "U1") (pin "76") (pinfunction "PA14/JTCK/SWCLK_76") (pintype "passive"))
    )
    (net (code "87") (name "/SWDIO") (class "Default")
      (node (ref "SWD") (pin "4") (pinfunction "4_4") (pintype "passive"))
      (node (ref "U1") (pin "72") (pinfunction "PA13/JTMS/SWDIO_72") (pintype "passive"))
    )
    (net (code "88") (name "3V3_DEBUG") (class "Default")
      (node (ref "Q3") (pin "3") (pinfunction "D_3") (pintype "passive"))
      (node (ref "SWD") (pin "5") (pinfunction "5_5") (pintype "passive"))
    )
    (net (code "89") (name "3V3_MCU") (class "Default")
      (node (ref "A") (pin "1") (pinfunction "1_1") (pintype "passive"))
      (node (ref "C32") (pin "2") (pinfunction "2_2") (pintype "passive"))
      (node (ref "C33") (pin "2") (pinfunction "2_2") (pintype "passive"))
      (node (ref "C34") (pin "2") (pinfunction "2_2") (pintype "passive"))
      (node (ref "C35") (pin "2") (pinfunction "2_2") (pintype "passive"))
      (node (ref "C36") (pin "2") (pinfunction "2_2") (pintype "passive"))
      (node (ref "C37") (pin "2") (pinfunction "2_2") (pintype "passive"))
      (node (ref "C38") (pin "2") (pinfunction "2_2") (pintype "passive"))
      (node (ref "C39") (pin "2") (pinfunction "2_2") (pintype "passive"))
      (node (ref "C40") (pin "2") (pinfunction "2_2") (pintype "passive"))
      (node (ref "C41") (pin "2") (pinfunction "2_2") (pintype "passive"))
      (node (ref "L2") (pin "2") (pinfunction "2_2") (pintype "passive"))
      (node (ref "LDO") (pin "5") (pinfunction "VOUT_5") (pintype "passive"))
      (node (ref "Q3") (pin "2") (pinfunction "S_2") (pintype "passive"))
      (node (ref "R13") (pin "2") (pinfunction "2_2") (pintype "passive"))
      (node (ref "R19") (pin "2") (pinfunction "2_2") (pintype "passive"))
      (node (ref "R27") (pin "1") (pinfunction "1_1") (pintype "passive"))
      (node (ref "R28") (pin "1") (pinfunction "1_1") (pintype "passive"))
      (node (ref "U1") (pin "100") (pinfunction "VDD_3_100") (pintype "passive"))
      (node (ref "U1") (pin "11") (pinfunction "VDD_5_11") (pintype "passive"))
      (node (ref "U1") (pin "19") (pinfunction "VDD12_19") (pintype "passive"))
      (node (ref "U1") (pin "28") (pinfunction "VDD_4_28") (pintype "passive"))
      (node (ref "U1") (pin "50") (pinfunction "VDD_1_50") (pintype "passive"))
      (node (ref "U1") (pin "6") (pinfunction "VBAT_6") (pintype "passive"))
      (node (ref "U1") (pin "75") (pinfunction "VDD_2_75") (pintype "passive"))
    )
    (net (code "90") (name "5V1") (class "Default")
      (node (ref "*") (pin "2") (pinfunction "VIN_2") (pintype "passive"))
      (node (ref "BLUETOOTH") (pin "4") (pinfunction "4_4") (pintype "passive"))
      (node (ref "BU") (pin "1") (pinfunction "0_1") (pintype "passive"))
      (node (ref "C11") (pin "2") (pinfunction "2_2") (pintype "passive"))
      (node (ref "C12") (pin "2") (pinfunction "2_2") (pintype "passive"))
      (node (ref "C13") (pin "2") (pinfunction "2_2") (pintype "passive"))
      (node (ref "C14") (pin "2") (pinfunction "2_2") (pintype "passive"))
      (node (ref "C15") (pin "2") (pinfunction "2_2") (pintype "passive"))
      (node (ref "C16") (pin "2") (pinfunction "2_2") (pintype "passive"))
      (node (ref "C17") (pin "2") (pinfunction "2_2") (pintype "passive"))
      (node (ref "C19") (pin "2") (pinfunction "2_2") (pintype "passive"))
      (node (ref "C2") (pin "2") (pinfunction "2_2") (pintype "passive"))
      (node (ref "C20") (pin "2") (pinfunction "2_2") (pintype "passive"))
      (node (ref "C21") (pin "2") (pinfunction "2_2") (pintype "passive"))
      (node (ref "C23") (pin "1") (pinfunction "1_1") (pintype "passive"))
      (node (ref "C24") (pin "2") (pinfunction "2_2") (pintype "passive"))
      (node (ref "C25") (pin "2") (pinfunction "2_2") (pintype "passive"))
      (node (ref "C3") (pin "2") (pinfunction "2_2") (pintype "passive"))
      (node (ref "C4") (pin "2") (pinfunction "2_2") (pintype "passive"))
      (node (ref "C5") (pin "2") (pinfunction "2_2") (pintype "passive"))
      (node (ref "C6") (pin "2") (pinfunction "2_2") (pintype "passive"))
      (node (ref "C7") (pin "2") (pinfunction "2_2") (pintype "passive"))
      (node (ref "C8") (pin "2") (pinfunction "2_2") (pintype "passive"))
      (node (ref "ENC1") (pin "1") (pinfunction "1_1") (pintype "passive"))
      (node (ref "ISO1") (pin "1") (pinfunction "VCC1_1") (pintype "passive"))
      (node (ref "ISO2") (pin "1") (pinfunction "VCC1_1") (pintype "passive"))
      (node (ref "ISO2") (pin "8") (pinfunction "VCC2_8") (pintype "passive"))
      (node (ref "L1") (pin "2") (pinfunction "2_2") (pintype "passive"))
      (node (ref "LDO") (pin "1") (pinfunction "VIN_1") (pintype "passive"))
      (node (ref "LDO") (pin "3") (pinfunction "EN_3") (pintype "passive"))
      (node (ref "MPU") (pin "11") (pinfunction "VCC_11") (pintype "passive"))
      (node (ref "MS1") (pin "1") (pinfunction "VIN_1") (pintype "passive"))
      (node (ref "OLED") (pin "1") (pinfunction "1_1") (pintype "passive"))
      (node (ref "Q2") (pin "2") (pinfunction "S_2") (pintype "passive"))
      (node (ref "Q3") (pin "1") (pinfunction "G_1") (pintype "passive"))
      (node (ref "R16") (pin "1") (pinfunction "1_1") (pintype "passive"))
      (node (ref "R5") (pin "2") (pinfunction "2_2") (pintype "passive"))
    )
    (net (code "91") (name "5V_ISO") (class "Default")
      (node (ref "*") (pin "4") (pinfunction "+V0_4") (pintype "passive"))
      (node (ref "C1") (pin "1") (pinfunction "1_1") (pintype "passive"))
      (node (ref "C9") (pin "1") (pinfunction "1_1") (pintype "passive"))
      (node (ref "ISO1") (pin "8") (pinfunction "VCC2_8") (pintype "passive"))
      (node (ref "MS1") (pin "6") (pinfunction "+V0_6") (pintype "passive"))
    )
    (net (code "92") (name "5V_USB") (class "Default")
      (node (ref "Q2") (pin "3") (pinfunction "D_3") (pintype "passive"))
      (node (ref "USB") (pin "1") (pinfunction "VCC_1") (pintype "passive"))
    )
    (net (code "93") (name "GND") (class "Default")
      (node (ref "*") (pin "1") (pinfunction "GND_1") (pintype "passive"))
      (node (ref "BLUETOOTH") (pin "3") (pinfunction "3_3") (pintype "passive"))
      (node (ref "BUCK1") (pin "7") (pinfunction "GND_7") (pintype "passive"))
      (node (ref "C10") (pin "1") (pinfunction "1_1") (pintype "passive"))
      (node (ref "C11") (pin "1") (pinfunction "1_1") (pintype "passive"))
      (node (ref "C12") (pin "1") (pinfunction "1_1") (pintype "passive"))
      (node (ref "C13") (pin "1") (pinfunction "1_1") (pintype "passive"))
      (node (ref "C14") (pin "1") (pinfunction "1_1") (pintype "passive"))
      (node (ref "C15") (pin "1") (pinfunction "1_1") (pintype "passive"))
      (node (ref "C16") (pin "1") (pinfunction "1_1") (pintype "passive"))
      (node (ref "C17") (pin "1") (pinfunction "1_1") (pintype "passive"))
      (node (ref "C18") (pin "2") (pinfunction "2_2") (pintype "passive"))
      (node (ref "C19") (pin "1") (pinfunction "1_1") (pintype "passive"))
      (node (ref "C2") (pin "1") (pinfunction "1_1") (pintype "passive"))
      (node (ref "C20") (pin "1") (pinfunction "1_1") (pintype "passive"))
      (node (ref "C21") (pin "1") (pinfunction "1_1") (pintype "passive"))
      (node (ref "C22") (pin "2") (pinfunction "2_2") (pintype "passive"))
      (node (ref "C23") (pin "2") (pinfunction "2_2") (pintype "passive"))
      (node (ref "C24") (pin "1") (pinfunction "1_1") (pintype "passive"))
      (node (ref "C25") (pin "1") (pinfunction "1_1") (pintype "passive"))
      (node (ref "C27") (pin "1") (pinfunction "1_1") (pintype "passive"))
      (node (ref "C28") (pin "1") (pinfunction "1_1") (pintype "passive"))
      (node (ref "C3") (pin "1") (pinfunction "1_1") (pintype "passive"))
      (node (ref "C30") (pin "2") (pinfunction "2_2") (pintype "passive"))
      (node (ref "C31") (pin "2") (pinfunction "2_2") (pintype "passive"))
      (node (ref "C32") (pin "1") (pinfunction "1_1") (pintype "passive"))
      (node (ref "C33") (pin "1") (pinfunction "1_1") (pintype "passive"))
      (node (ref "C34") (pin "1") (pinfunction "1_1") (pintype "passive"))
      (node (ref "C35") (pin "1") (pinfunction "1_1") (pintype "passive"))
      (node (ref "C36") (pin "1") (pinfunction "1_1") (pintype "passive"))
      (node (ref "C37") (pin "1") (pinfunction "1_1") (pintype "passive"))
      (node (ref "C38") (pin "1") (pinfunction "1_1") (pintype "passive"))
      (node (ref "C39") (pin "1") (pinfunction "1_1") (pintype "passive"))
      (node (ref "C4") (pin "1") (pinfunction "1_1") (pintype "passive"))
      (node (ref "C40") (pin "1") (pinfunction "1_1") (pintype "passive"))
      (node (ref "C41") (pin "1") (pinfunction "1_1") (pintype "passive"))
      (node (ref "C42") (pin "1") (pinfunction "1_1") (pintype "passive"))
      (node (ref "C43") (pin "1") (pinfunction "1_1") (pintype "passive"))
      (node (ref "C44") (pin "1") (pinfunction "1_1") (pintype "passive"))
      (node (ref "C45") (pin "1") (pinfunction "1_1") (pintype "passive"))
      (node (ref "C46") (pin "1") (pinfunction "1_1") (pintype "passive"))
      (node (ref "C5") (pin "1") (pinfunction "1_1") (pintype "passive"))
      (node (ref "C6") (pin "1") (pinfunction "1_1") (pintype "passive"))
      (node (ref "C7") (pin "1") (pinfunction "1_1") (pintype "passive"))
      (node (ref "C8") (pin "1") (pinfunction "1_1") (pintype "passive"))
      (node (ref "CLOSED") (pin "2") (pinfunction "K_2") (pintype "passive"))
      (node (ref "D4") (pin "1") (pinfunction "A_1") (pintype "passive"))
      (node (ref "DISM") (pin "1") (pinfunction "1_1") (pintype "passive"))
      (node (ref "ENC1") (pin "2") (pinfunction "2_2") (pintype "passive"))
      (node (ref "ERR_RED") (pin "1") (pinfunction "A_1") (pintype "passive"))
      (node (ref "HG1") (pin "2") (pinfunction "2_2") (pintype "passive"))
      (node (ref "HG1") (pin "3") (pinfunction "3_3") (pintype "passive"))
      (node (ref "HG2") (pin "2") (pinfunction "2_2") (pintype "passive"))
      (node (ref "HG2") (pin "3") (pinfunction "3_3") (pintype "passive"))
      (node (ref "ISO1") (pin "4") (pinfunction "GND1_4") (pintype "passive"))
      (node (ref "ISO2") (pin "4") (pinfunction "GND1_4") (pintype "passive"))
      (node (ref "ISO2") (pin "5") (pinfunction "GND2_5") (pintype "passive"))
      (node (ref "L3") (pin "1") (pinfunction "1_1") (pintype "passive"))
      (node (ref "LDO") (pin "2") (pinfunction "GND_2") (pintype "passive"))
      (node (ref "LX") (pin "3") (pinfunction "3_3") (pintype "passive"))
      (node (ref "MPU") (pin "8") (pinfunction "GND_8") (pintype "passive"))
      (node (ref "MS1") (pin "2") (pinfunction "GND_2") (pintype "passive"))
      (node (ref "OK_GREEN") (pin "2") (pinfunction "K_2") (pintype "passive"))
      (node (ref "OLED") (pin "2") (pinfunction "2_2") (pintype "passive"))
      (node (ref "POWER") (pin "1") (pinfunction "1_1") (pintype "passive"))
      (node (ref "Q1") (pin "2") (pinfunction "S_2") (pintype "passive"))
      (node (ref "R11") (pin "2") (pinfunction "2_2") (pintype "passive"))
      (node (ref "R12") (pin "2") (pinfunction "2_2") (pintype "passive"))
      (node (ref "R14") (pin "2") (pinfunction "2_2") (pintype "passive"))
      (node (ref "R15") (pin "2") (pinfunction "2_2") (pintype "passive"))
      (node (ref "R17") (pin "1") (pinfunction "1_1") (pintype "passive"))
      (node (ref "R18") (pin "1") (pinfunction "1_1") (pintype "passive"))
      (node (ref "R39") (pin "2") (pinfunction "2_2") (pintype "passive"))
      (node (ref "RUN") (pin "2") (pinfunction "K_2") (pintype "passive"))
      (node (ref "S1") (pin "3") (pinfunction "3_3") (pintype "passive"))
      (node (ref "SRST") (pin "1") (pinfunction "1_1") (pintype "passive"))
      (node (ref "SWD") (pin "2") (pinfunction "2_2") (pintype "passive"))
      (node (ref "U1") (pin "10") (pinfunction "VSS_5_10") (pintype "passive"))
      (node (ref "U1") (pin "27") (pinfunction "VSS_4_27") (pintype "passive"))
      (node (ref "U1") (pin "74") (pinfunction "VSS_2_74") (pintype "passive"))
      (node (ref "U1") (pin "94") (pinfunction "BOOT0_94") (pintype "passive"))
      (node (ref "USB") (pin "5") (pinfunction "VSS_5") (pintype "passive"))
      (node (ref "Z") (pin "2") (pinfunction "2_2") (pintype "passive"))
    )
    (net (code "94") (name "GND_ISO") (class "Default")
      (node (ref "*") (pin "3") (pinfunction "0V_3") (pintype "passive"))
      (node (ref "C1") (pin "2") (pinfunction "2_2") (pintype "passive"))
      (node (ref "C9") (pin "2") (pinfunction "2_2") (pintype "passive"))
      (node (ref "ISO1") (pin "5") (pinfunction "GND2_5") (pintype "passive"))
      (node (ref "MS1") (pin "4") (pinfunction "0V_4") (pintype "passive"))
    )
    (net (code "95") (name "Net-(BU-1)") (class "Default")
      (node (ref "BU") (pin "2") (pinfunction "1_2") (pintype "passive"))
      (node (ref "Q1") (pin "3") (pinfunction "D_3") (pintype "passive"))
    )
    (net (code "96") (name "Net-(BUCK1-BOOT)") (class "Default")
      (node (ref "BUCK1") (pin "1") (pinfunction "BOOT_1") (pintype "passive"))
      (node (ref "C26") (pin "2") (pinfunction "2_2") (pintype "passive"))
    )
    (net (code "97") (name "Net-(BUCK1-COMP)") (class "Default")
      (node (ref "BUCK1") (pin "6") (pinfunction "COMP_6") (pintype "passive"))
      (node (ref "C28") (pin "2") (pinfunction "2_2") (pintype "passive"))
      (node (ref "C29") (pin "2") (pinfunction "2_2") (pintype "passive"))
    )
    (net (code "98") (name "Net-(BUCK1-EN)") (class "Default")
      (node (ref "BUCK1") (pin "3") (pinfunction "EN_3") (pintype "passive"))
      (node (ref "R10") (pin "2") (pinfunction "2_2") (pintype "passive"))
      (node (ref "R14") (pin "1") (pinfunction "1_1") (pintype "passive"))
    )
    (net (code "99") (name "Net-(BUCK1-PH)") (class "Default")
      (node (ref "BUCK1") (pin "8") (pinfunction "PH_8") (pintype "passive"))
      (node (ref "C26") (pin "1") (pinfunction "1_1") (pintype "passive"))
      (node (ref "D4") (pin "2") (pinfunction "K_2") (pintype "passive"))
      (node (ref "L1") (pin "1") (pinfunction "1_1") (pintype "passive"))
    )
    (net (code "100") (name "Net-(BUCK1-SS)") (class "Default")
      (node (ref "BUCK1") (pin "4") (pinfunction "SS_4") (pintype "passive"))
      (node (ref "C27") (pin "2") (pinfunction "2_2") (pintype "passive"))
    )
    (net (code "101") (name "Net-(BUCK1-VSENSE)") (class "Default")
      (node (ref "BUCK1") (pin "5") (pinfunction "VSENSE_5") (pintype "passive"))
      (node (ref "R15") (pin "1") (pinfunction "1_1") (pintype "passive"))
      (node (ref "R16") (pin "2") (pinfunction "2_2") (pintype "passive"))
    )
    (net (code "102") (name "Net-(C29-Pad1)") (class "Default")
      (node (ref "C29") (pin "1") (pinfunction "1_1") (pintype "passive"))
      (node (ref "R17") (pin "2") (pinfunction "2_2") (pintype "passive"))
    )
    (net (code "103") (name "Net-(CLOSED-A)") (class "Default")
      (node (ref "CLOSED") (pin "1") (pinfunction "A_1") (pintype "passive"))
      (node (ref "R4") (pin "1") (pinfunction "1_1") (pintype "passive"))
    )
    (net (code "104") (name "Net-(ERR_RED-K)") (class "Default")
      (node (ref "ERR_RED") (pin "2") (pinfunction "K_2") (pintype "passive"))
      (node (ref "R2") (pin "2") (pinfunction "2_2") (pintype "passive"))
    )
    (net (code "105") (name "Net-(HG1-Pad1)") (class "Default")
      (node (ref "HG1") (pin "1") (pinfunction "1_1") (pintype "passive"))
      (node (ref "R37") (pin "1") (pinfunction "1_1") (pintype "passive"))
    )
    (net (code "106") (name "Net-(HG2-Pad1)") (class "Default")
      (node (ref "HG2") (pin "1") (pinfunction "1_1") (pintype "passive"))
      (node (ref "R38") (pin "1") (pinfunction "1_1") (pintype "passive"))
    )
    (net (code "107") (name "Net-(ISO1-CANH)") (class "Default")
      (node (ref "ISO1") (pin "7") (pinfunction "CANH_7") (pintype "passive"))
      (node (ref "R30") (pin "2") (pinfunction "2_2") (pintype "passive"))
    )
    (net (code "108") (name "Net-(ISO1-CANL)") (class "Default")
      (node (ref "ISO1") (pin "6") (pinfunction "CANL_6") (pintype "passive"))
      (node (ref "R31") (pin "2") (pinfunction "2_2") (pintype "passive"))
    )
    (net (code "109") (name "Net-(ISO2-CANH)") (class "Default")
      (node (ref "ISO2") (pin "7") (pinfunction "CANH_7") (pintype "passive"))
      (node (ref "R7") (pin "2") (pinfunction "2_2") (pintype "passive"))
    )
    (net (code "110") (name "Net-(ISO2-CANL)") (class "Default")
      (node (ref "ISO2") (pin "6") (pinfunction "CANL_6") (pintype "passive"))
      (node (ref "R8") (pin "2") (pinfunction "2_2") (pintype "passive"))
    )
    (net (code "111") (name "Net-(LDO-BP)") (class "Default")
      (node (ref "C10") (pin "2") (pinfunction "2_2") (pintype "passive"))
      (node (ref "LDO") (pin "4") (pinfunction "BP_4") (pintype "passive"))
    )
    (net (code "112") (name "Net-(LX-Pad2)") (class "Default")
      (node (ref "LX") (pin "2") (pinfunction "2_2") (pintype "passive"))
      (node (ref "R39") (pin "1") (pinfunction "1_1") (pintype "passive"))
    )
    (net (code "113") (name "Net-(OK_GREEN-A)") (class "Default")
      (node (ref "OK_GREEN") (pin "1") (pinfunction "A_1") (pintype "passive"))
      (node (ref "R1") (pin "2") (pinfunction "2_2") (pintype "passive"))
    )
    (net (code "114") (name "Net-(Q2-G)") (class "Default")
      (node (ref "Q2") (pin "1") (pinfunction "G_1") (pintype "passive"))
      (node (ref "R18") (pin "2") (pinfunction "2_2") (pintype "passive"))
      (node (ref "R9") (pin "1") (pinfunction "1_1") (pintype "passive"))
    )
    (net (code "115") (name "Net-(RUN-A)") (class "Default")
      (node (ref "R5") (pin "1") (pinfunction "1_1") (pintype "passive"))
      (node (ref "RUN") (pin "1") (pinfunction "A_1") (pintype "passive"))
    )
    (net (code "116") (name "Net-(U1B-PDR_ON)") (class "Default")
      (node (ref "A") (pin "2") (pinfunction "2_2") (pintype "passive"))
      (node (ref "U1") (pin "99") (pinfunction "PDR_ON_99") (pintype "passive"))
      (node (ref "Z") (pin "1") (pinfunction "1_1") (pintype "passive"))
    )
    (net (code "117") (name "Net-(U1B-VCAP1)") (class "Default")
      (node (ref "C30") (pin "1") (pinfunction "1_1") (pintype "passive"))
      (node (ref "U1") (pin "49") (pinfunction "VCAP1_49") (pintype "passive"))
    )
    (net (code "118") (name "Net-(U1B-VCAP2)") (class "Default")
      (node (ref "C31") (pin "1") (pinfunction "1_1") (pintype "passive"))
      (node (ref "U1") (pin "73") (pinfunction "VCAP2_73") (pintype "passive"))
    )
    (net (code "119") (name "Net-(U1B-VDDA)") (class "Default")
      (node (ref "L2") (pin "1") (pinfunction "1_1") (pintype "passive"))
      (node (ref "U1") (pin "21") (pinfunction "VREF+_21") (pintype "passive"))
      (node (ref "U1") (pin "22") (pinfunction "VDDA_22") (pintype "passive"))
    )
    (net (code "120") (name "Net-(U1B-VSSA)") (class "Default")
      (node (ref "L3") (pin "2") (pinfunction "2_2") (pintype "passive"))
      (node (ref "U1") (pin "20") (pinfunction "VSSA_20") (pintype "passive"))
    )
    (net (code "121") (name "POWER+") (class "Default")
      (node (ref "D3") (pin "2") (pinfunction "K_2") (pintype "passive"))
      (node (ref "R9") (pin "2") (pinfunction "2_2") (pintype "passive"))
      (node (ref "SW") (pin "1") (pinfunction "NO1_1") (pintype "passive"))
    )
    (net (code "122") (name "POWER_ERR") (class "Default")
      (node (ref "D3") (pin "1") (pinfunction "A_1") (pintype "passive"))
      (node (ref "POWER") (pin "2") (pinfunction "2_2") (pintype "passive"))
      (node (ref "R1") (pin "1") (pinfunction "1_1") (pintype "passive"))
      (node (ref "R2") (pin "1") (pinfunction "1_1") (pintype "passive"))
    )
    (net (code "123") (name "V+") (class "Default")
      (node (ref "FUSE") (pin "2") (pinfunction "2_2") (pintype "passive"))
      (node (ref "R4") (pin "2") (pinfunction "2_2") (pintype "passive"))
      (node (ref "SW") (pin "2") (pinfunction "COMMON_2") (pintype "passive"))
      (node (ref "SW") (pin "3") (pinfunction "NO2_3") (pintype "passive"))
    )
    (net (code "124") (name "VIN") (class "Default")
      (node (ref "BUCK1") (pin "2") (pinfunction "VIN_2") (pintype "passive"))
      (node (ref "C18") (pin "1") (pinfunction "1_1") (pintype "passive"))
      (node (ref "C22") (pin "1") (pinfunction "1_1") (pintype "passive"))
      (node (ref "FUSE") (pin "1") (pinfunction "1_1") (pintype "passive"))
      (node (ref "HG1") (pin "4") (pinfunction "4_4") (pintype "passive"))
      (node (ref "HG2") (pin "4") (pinfunction "4_4") (pintype "passive"))
      (node (ref "LX") (pin "4") (pinfunction "4_4") (pintype "passive"))
      (node (ref "R10") (pin "1") (pinfunction "1_1") (pintype "passive"))
    )
    (net (code "125") (name "unconnected-(S1-Pad1)") (class "Default")
      (node (ref "S1") (pin "1") (pinfunction "1_1") (pintype "passive"))
    )
    (net (code "126") (name "unconnected-(S1-Pad2)") (class "Default")
      (node (ref "S1") (pin "2") (pinfunction "2_2") (pintype "passive"))
    )
    (net (code "127") (name "unconnected-(USB-D+-Pad3)") (class "Default")
      (node (ref "USB") (pin "3") (pinfunction "D+_3") (pintype "passive"))
    )
    (net (code "128") (name "unconnected-(USB-D--Pad2)") (class "Default")
      (node (ref "USB") (pin "2") (pinfunction "D-_2") (pintype "passive"))
    )
    (net (code "129") (name "unconnected-(USB-ID-Pad4)") (class "Default")
      (node (ref "USB") (pin "4") (pinfunction "ID_4") (pintype "passive"))
    )
  )
)
